# MBO.net
KiCad netlist of a schematic drawn in EAGLE
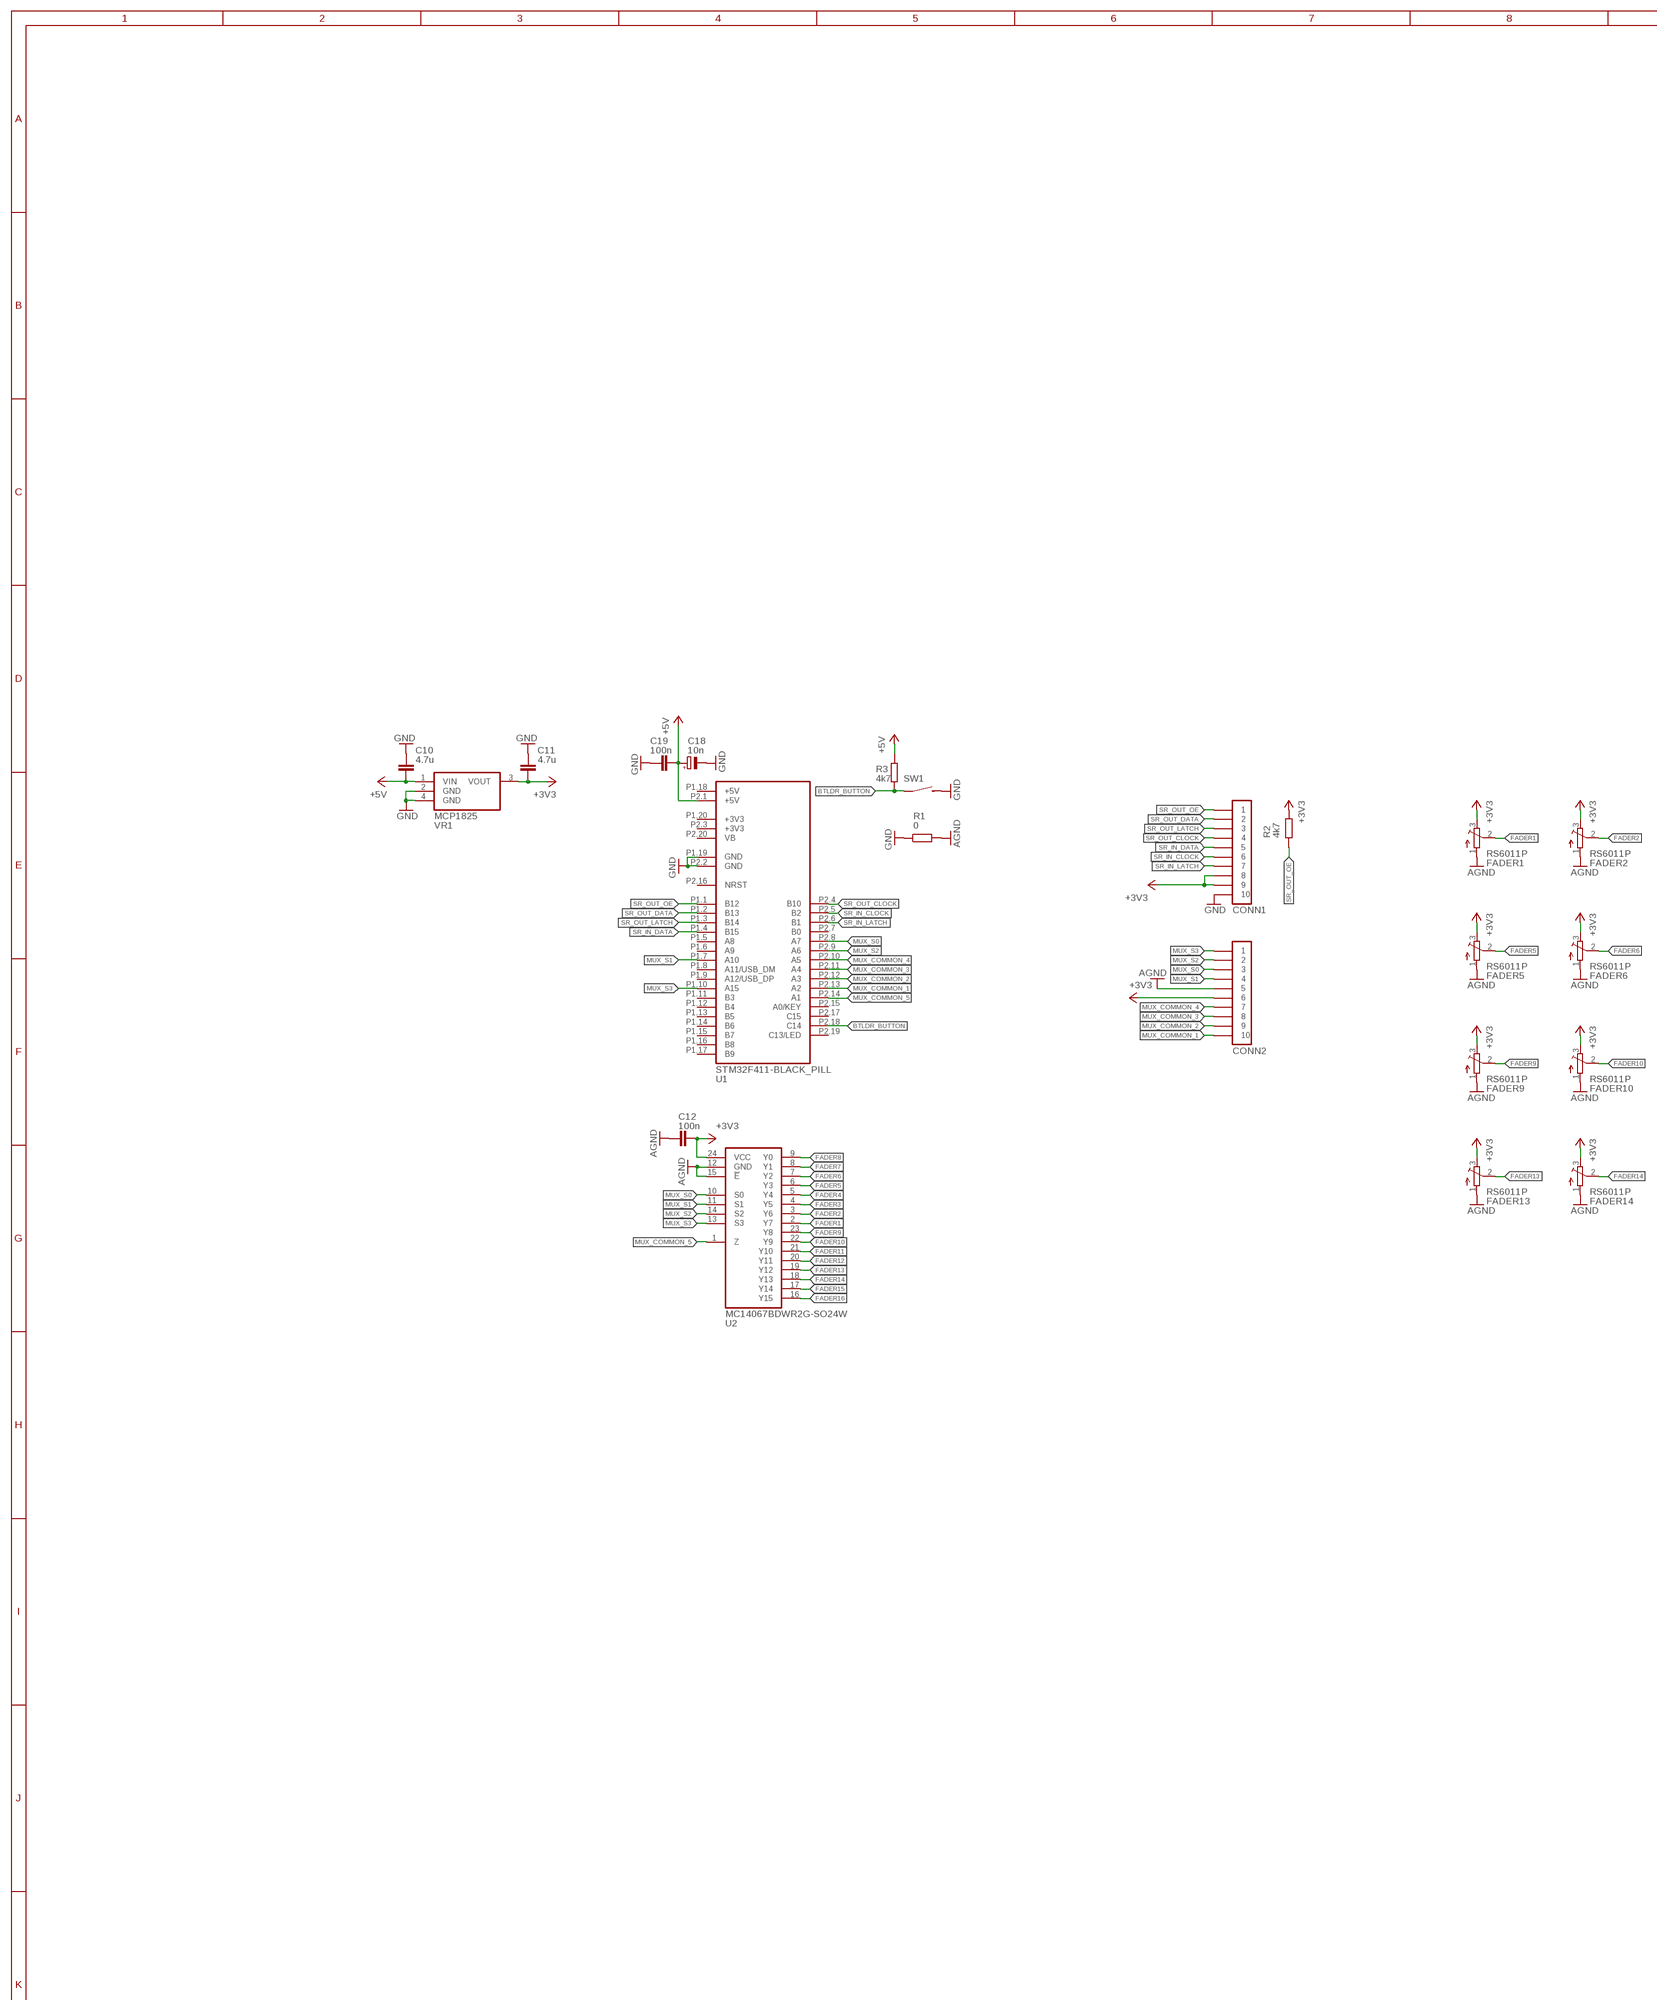
[diagram p0: schematic, sheet 1, part 1 of 3]
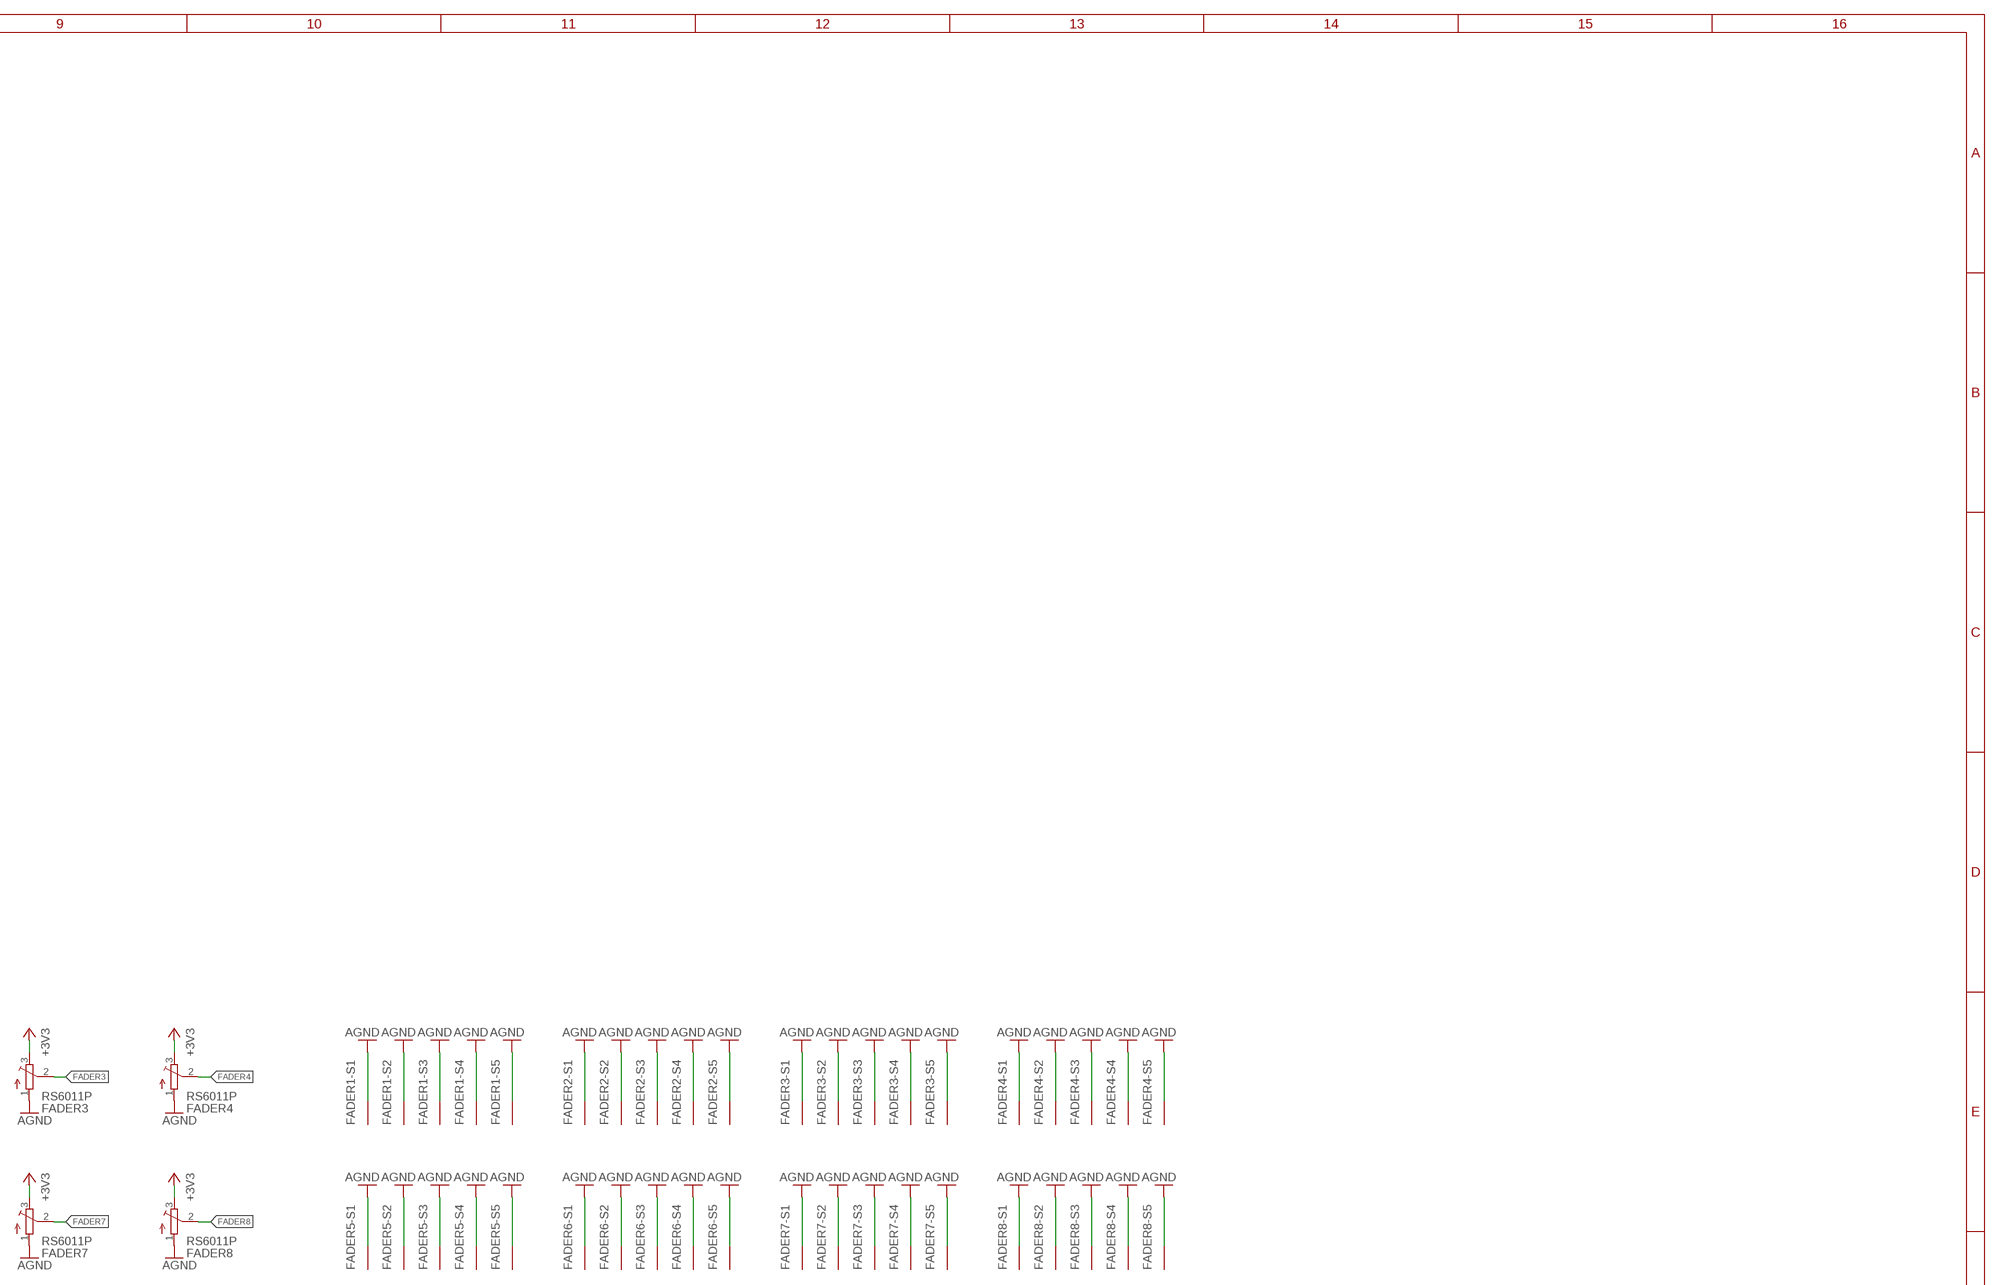
[diagram p1: schematic, sheet 1, part 2 of 3]
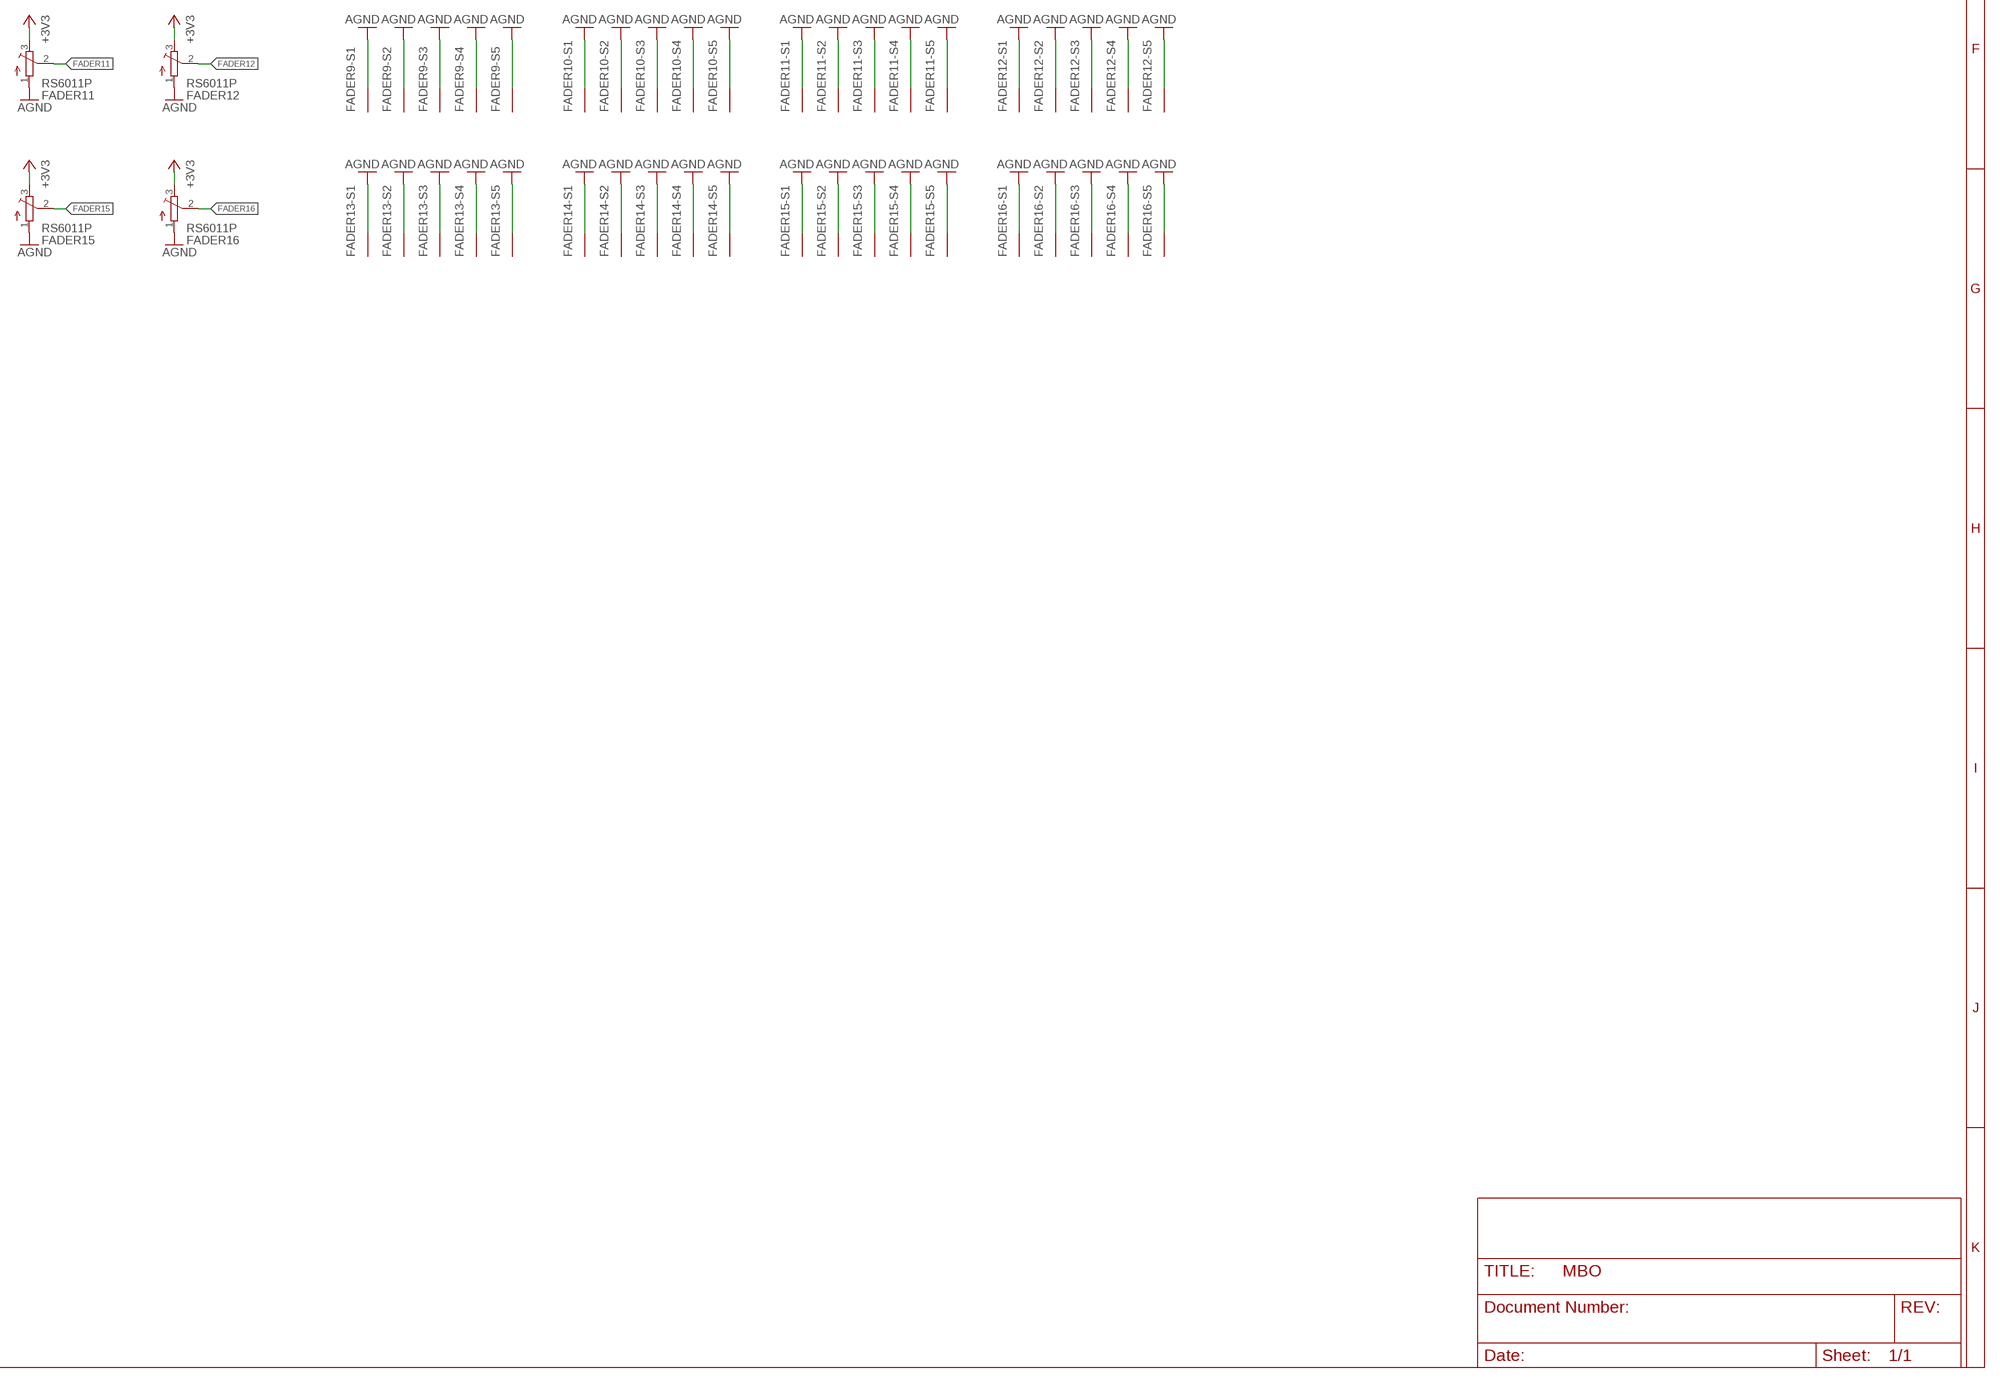
[diagram p2: schematic, sheet 1, part 3 of 3]

(export (version "E")
  (design (tool "Eeschema 10.0.6"))
  (components
    (comp (ref "C10")
      (value "4.7u")
      (footprint "eagle-import:C0805")
      (libsource (lib "eagle-import") (part "CAPACITOR-0805"))
    )
    (comp (ref "C11")
      (value "4.7u")
      (footprint "eagle-import:C0805")
      (libsource (lib "eagle-import") (part "CAPACITOR-0805"))
    )
    (comp (ref "C12")
      (value "100n")
      (footprint "eagle-import:C0805")
      (libsource (lib "eagle-import") (part "CAPACITOR-0805"))
    )
    (comp (ref "C18")
      (value "10n")
      (footprint "eagle-import:C-TH-E-0401")
      (libsource (lib "eagle-import") (part "ELECTROLYTIC_CAPACITOR-C-TH-E-0401"))
    )
    (comp (ref "C19")
      (value "100n")
      (footprint "eagle-import:C0805")
      (libsource (lib "eagle-import") (part "CAPACITOR-0805"))
    )
    (comp (ref "CONN1")
      (value "PINHD-1X10-FFC-1MM-Z")
      (footprint "eagle-import:MOLEX-52271-1079")
      (fields (field (name "MANUFACTURER") "Molex") (field (name "MPN") "52271-1079"))
      (libsource (lib "eagle-import") (part "PINHD-1X10-FFC-1MM-Z"))
    )
    (comp (ref "CONN2")
      (value "PINHD-1X10-FFC-1MM-Z")
      (footprint "eagle-import:MOLEX-52271-1079")
      (fields (field (name "MANUFACTURER") "Molex") (field (name "MPN") "52271-1079"))
      (libsource (lib "eagle-import") (part "PINHD-1X10-FFC-1MM-Z"))
    )
    (comp (ref "FADER1")
      (value "RS6011P")
      (footprint "eagle-import:RS6011_P")
      (libsource (lib "eagle-import") (part "RS6011P"))
    )
    (comp (ref "FADER2")
      (value "RS6011P")
      (footprint "eagle-import:RS6011_P")
      (libsource (lib "eagle-import") (part "RS6011P"))
    )
    (comp (ref "FADER3")
      (value "RS6011P")
      (footprint "eagle-import:RS6011_P")
      (libsource (lib "eagle-import") (part "RS6011P"))
    )
    (comp (ref "FADER4")
      (value "RS6011P")
      (footprint "eagle-import:RS6011_P")
      (libsource (lib "eagle-import") (part "RS6011P"))
    )
    (comp (ref "FADER5")
      (value "RS6011P")
      (footprint "eagle-import:RS6011_P")
      (libsource (lib "eagle-import") (part "RS6011P"))
    )
    (comp (ref "FADER6")
      (value "RS6011P")
      (footprint "eagle-import:RS6011_P")
      (libsource (lib "eagle-import") (part "RS6011P"))
    )
    (comp (ref "FADER7")
      (value "RS6011P")
      (footprint "eagle-import:RS6011_P")
      (libsource (lib "eagle-import") (part "RS6011P"))
    )
    (comp (ref "FADER8")
      (value "RS6011P")
      (footprint "eagle-import:RS6011_P")
      (libsource (lib "eagle-import") (part "RS6011P"))
    )
    (comp (ref "FADER9")
      (value "RS6011P")
      (footprint "eagle-import:RS6011_P")
      (libsource (lib "eagle-import") (part "RS6011P"))
    )
    (comp (ref "FADER10")
      (value "RS6011P")
      (footprint "eagle-import:RS6011_P")
      (libsource (lib "eagle-import") (part "RS6011P"))
    )
    (comp (ref "FADER11")
      (value "RS6011P")
      (footprint "eagle-import:RS6011_P")
      (libsource (lib "eagle-import") (part "RS6011P"))
    )
    (comp (ref "FADER12")
      (value "RS6011P")
      (footprint "eagle-import:RS6011_P")
      (libsource (lib "eagle-import") (part "RS6011P"))
    )
    (comp (ref "FADER13")
      (value "RS6011P")
      (footprint "eagle-import:RS6011_P")
      (libsource (lib "eagle-import") (part "RS6011P"))
    )
    (comp (ref "FADER14")
      (value "RS6011P")
      (footprint "eagle-import:RS6011_P")
      (libsource (lib "eagle-import") (part "RS6011P"))
    )
    (comp (ref "FADER15")
      (value "RS6011P")
      (footprint "eagle-import:RS6011_P")
      (libsource (lib "eagle-import") (part "RS6011P"))
    )
    (comp (ref "FADER16")
      (value "RS6011P")
      (footprint "eagle-import:RS6011_P")
      (libsource (lib "eagle-import") (part "RS6011P"))
    )
    (comp (ref "R1")
      (value "0")
      (footprint "eagle-import:R0805")
      (libsource (lib "eagle-import") (part "RESISTOR-0805"))
    )
    (comp (ref "R2")
      (value "4k7")
      (footprint "eagle-import:R0805")
      (libsource (lib "eagle-import") (part "RESISTOR-0805"))
    )
    (comp (ref "R3")
      (value "4k7")
      (footprint "eagle-import:R0805")
      (libsource (lib "eagle-import") (part "RESISTOR-0805"))
    )
    (comp (ref "SW1")
      (value "SWITCH-TACT-TH-6X6MM")
      (footprint "eagle-import:TACT_SW_6X6MM")
      (libsource (lib "eagle-import") (part "SWITCH-TACT-TH-6X6MM"))
    )
    (comp (ref "U1")
      (value "STM32F411-BLACK_PILL")
      (footprint "eagle-import:STM32F411-BLACK_PILL")
      (libsource (lib "eagle-import") (part "STM32F411-BLACK_PILL"))
    )
    (comp (ref "U2")
      (value "MC14067BDWR2G-SO24W")
      (footprint "eagle-import:SO24-W")
      (fields (field (name "MANUFACTURER") "ON Semiconductor") (field (name "MPN") "MC14067BDWR2G"))
      (libsource (lib "eagle-import") (part "MC14067BDWR2G-SO24W"))
    )
    (comp (ref "VR1")
      (value "MCP1825")
      (footprint "eagle-import:SOT223")
      (fields (field (name "MANUFACTURER") "Microchip") (field (name "MPN") "MCP1825S-3302E/DB"))
      (libsource (lib "eagle-import") (part "MCP1825"))
    )
  )
  (nets
    (net (code "1") (name "+3V3") (class "Default")
      (node (ref "C11") (pin "1") (pinfunction "1_1") (pintype "passive"))
      (node (ref "C12") (pin "1") (pinfunction "1_1") (pintype "passive"))
      (node (ref "CONN1") (pin "8") (pinfunction "8_8") (pintype "passive"))
      (node (ref "CONN1") (pin "9") (pinfunction "9_9") (pintype "passive"))
      (node (ref "CONN2") (pin "6") (pinfunction "6_6") (pintype "passive"))
      (node (ref "FADER1") (pin "3") (pinfunction "3_3") (pintype "passive"))
      (node (ref "FADER10") (pin "3") (pinfunction "3_3") (pintype "passive"))
      (node (ref "FADER11") (pin "3") (pinfunction "3_3") (pintype "passive"))
      (node (ref "FADER12") (pin "3") (pinfunction "3_3") (pintype "passive"))
      (node (ref "FADER13") (pin "3") (pinfunction "3_3") (pintype "passive"))
      (node (ref "FADER14") (pin "3") (pinfunction "3_3") (pintype "passive"))
      (node (ref "FADER15") (pin "3") (pinfunction "3_3") (pintype "passive"))
      (node (ref "FADER16") (pin "3") (pinfunction "3_3") (pintype "passive"))
      (node (ref "FADER2") (pin "3") (pinfunction "3_3") (pintype "passive"))
      (node (ref "FADER3") (pin "3") (pinfunction "3_3") (pintype "passive"))
      (node (ref "FADER4") (pin "3") (pinfunction "3_3") (pintype "passive"))
      (node (ref "FADER5") (pin "3") (pinfunction "3_3") (pintype "passive"))
      (node (ref "FADER6") (pin "3") (pinfunction "3_3") (pintype "passive"))
      (node (ref "FADER7") (pin "3") (pinfunction "3_3") (pintype "passive"))
      (node (ref "FADER8") (pin "3") (pinfunction "3_3") (pintype "passive"))
      (node (ref "FADER9") (pin "3") (pinfunction "3_3") (pintype "passive"))
      (node (ref "R2") (pin "2") (pinfunction "2_2") (pintype "passive"))
      (node (ref "U2") (pin "24") (pinfunction "VCC_24") (pintype "passive"))
      (node (ref "VR1") (pin "3") (pinfunction "VOUT_3") (pintype "passive"))
    )
    (net (code "2") (name "+5V") (class "Default")
      (node (ref "C10") (pin "1") (pinfunction "1_1") (pintype "passive"))
      (node (ref "C18") (pin "+") (pinfunction "+_+") (pintype "passive"))
      (node (ref "C19") (pin "1") (pinfunction "1_1") (pintype "passive"))
      (node (ref "R3") (pin "1") (pinfunction "1_1") (pintype "passive"))
      (node (ref "U1") (pin "P2.1") (pinfunction "+5V_P2.1") (pintype "bidirectional"))
      (node (ref "VR1") (pin "1") (pinfunction "VIN_1") (pintype "passive"))
    )
    (net (code "3") (name "AGND") (class "Default")
      (node (ref "C12") (pin "2") (pinfunction "2_2") (pintype "passive"))
      (node (ref "CONN2") (pin "5") (pinfunction "5_5") (pintype "passive"))
      (node (ref "FADER1") (pin "1") (pinfunction "1_1") (pintype "passive"))
      (node (ref "FADER1") (pin "S1") (pinfunction "S_S1") (pintype "passive"))
      (node (ref "FADER1") (pin "S2") (pinfunction "S_S2") (pintype "passive"))
      (node (ref "FADER1") (pin "S3") (pinfunction "S_S3") (pintype "passive"))
      (node (ref "FADER1") (pin "S4") (pinfunction "S_S4") (pintype "passive"))
      (node (ref "FADER1") (pin "S5") (pinfunction "S_S5") (pintype "passive"))
      (node (ref "FADER10") (pin "1") (pinfunction "1_1") (pintype "passive"))
      (node (ref "FADER10") (pin "S1") (pinfunction "S_S1") (pintype "passive"))
      (node (ref "FADER10") (pin "S2") (pinfunction "S_S2") (pintype "passive"))
      (node (ref "FADER10") (pin "S3") (pinfunction "S_S3") (pintype "passive"))
      (node (ref "FADER10") (pin "S4") (pinfunction "S_S4") (pintype "passive"))
      (node (ref "FADER10") (pin "S5") (pinfunction "S_S5") (pintype "passive"))
      (node (ref "FADER11") (pin "1") (pinfunction "1_1") (pintype "passive"))
      (node (ref "FADER11") (pin "S1") (pinfunction "S_S1") (pintype "passive"))
      (node (ref "FADER11") (pin "S2") (pinfunction "S_S2") (pintype "passive"))
      (node (ref "FADER11") (pin "S3") (pinfunction "S_S3") (pintype "passive"))
      (node (ref "FADER11") (pin "S4") (pinfunction "S_S4") (pintype "passive"))
      (node (ref "FADER11") (pin "S5") (pinfunction "S_S5") (pintype "passive"))
      (node (ref "FADER12") (pin "1") (pinfunction "1_1") (pintype "passive"))
      (node (ref "FADER12") (pin "S1") (pinfunction "S_S1") (pintype "passive"))
      (node (ref "FADER12") (pin "S2") (pinfunction "S_S2") (pintype "passive"))
      (node (ref "FADER12") (pin "S3") (pinfunction "S_S3") (pintype "passive"))
      (node (ref "FADER12") (pin "S4") (pinfunction "S_S4") (pintype "passive"))
      (node (ref "FADER12") (pin "S5") (pinfunction "S_S5") (pintype "passive"))
      (node (ref "FADER13") (pin "1") (pinfunction "1_1") (pintype "passive"))
      (node (ref "FADER13") (pin "S1") (pinfunction "S_S1") (pintype "passive"))
      (node (ref "FADER13") (pin "S2") (pinfunction "S_S2") (pintype "passive"))
      (node (ref "FADER13") (pin "S3") (pinfunction "S_S3") (pintype "passive"))
      (node (ref "FADER13") (pin "S4") (pinfunction "S_S4") (pintype "passive"))
      (node (ref "FADER13") (pin "S5") (pinfunction "S_S5") (pintype "passive"))
      (node (ref "FADER14") (pin "1") (pinfunction "1_1") (pintype "passive"))
      (node (ref "FADER14") (pin "S1") (pinfunction "S_S1") (pintype "passive"))
      (node (ref "FADER14") (pin "S2") (pinfunction "S_S2") (pintype "passive"))
      (node (ref "FADER14") (pin "S3") (pinfunction "S_S3") (pintype "passive"))
      (node (ref "FADER14") (pin "S4") (pinfunction "S_S4") (pintype "passive"))
      (node (ref "FADER14") (pin "S5") (pinfunction "S_S5") (pintype "passive"))
      (node (ref "FADER15") (pin "1") (pinfunction "1_1") (pintype "passive"))
      (node (ref "FADER15") (pin "S1") (pinfunction "S_S1") (pintype "passive"))
      (node (ref "FADER15") (pin "S2") (pinfunction "S_S2") (pintype "passive"))
      (node (ref "FADER15") (pin "S3") (pinfunction "S_S3") (pintype "passive"))
      (node (ref "FADER15") (pin "S4") (pinfunction "S_S4") (pintype "passive"))
      (node (ref "FADER15") (pin "S5") (pinfunction "S_S5") (pintype "passive"))
      (node (ref "FADER16") (pin "1") (pinfunction "1_1") (pintype "passive"))
      (node (ref "FADER16") (pin "S1") (pinfunction "S_S1") (pintype "passive"))
      (node (ref "FADER16") (pin "S2") (pinfunction "S_S2") (pintype "passive"))
      (node (ref "FADER16") (pin "S3") (pinfunction "S_S3") (pintype "passive"))
      (node (ref "FADER16") (pin "S4") (pinfunction "S_S4") (pintype "passive"))
      (node (ref "FADER16") (pin "S5") (pinfunction "S_S5") (pintype "passive"))
      (node (ref "FADER2") (pin "1") (pinfunction "1_1") (pintype "passive"))
      (node (ref "FADER2") (pin "S1") (pinfunction "S_S1") (pintype "passive"))
      (node (ref "FADER2") (pin "S2") (pinfunction "S_S2") (pintype "passive"))
      (node (ref "FADER2") (pin "S3") (pinfunction "S_S3") (pintype "passive"))
      (node (ref "FADER2") (pin "S4") (pinfunction "S_S4") (pintype "passive"))
      (node (ref "FADER2") (pin "S5") (pinfunction "S_S5") (pintype "passive"))
      (node (ref "FADER3") (pin "1") (pinfunction "1_1") (pintype "passive"))
      (node (ref "FADER3") (pin "S1") (pinfunction "S_S1") (pintype "passive"))
      (node (ref "FADER3") (pin "S2") (pinfunction "S_S2") (pintype "passive"))
      (node (ref "FADER3") (pin "S3") (pinfunction "S_S3") (pintype "passive"))
      (node (ref "FADER3") (pin "S4") (pinfunction "S_S4") (pintype "passive"))
      (node (ref "FADER3") (pin "S5") (pinfunction "S_S5") (pintype "passive"))
      (node (ref "FADER4") (pin "1") (pinfunction "1_1") (pintype "passive"))
      (node (ref "FADER4") (pin "S1") (pinfunction "S_S1") (pintype "passive"))
      (node (ref "FADER4") (pin "S2") (pinfunction "S_S2") (pintype "passive"))
      (node (ref "FADER4") (pin "S3") (pinfunction "S_S3") (pintype "passive"))
      (node (ref "FADER4") (pin "S4") (pinfunction "S_S4") (pintype "passive"))
      (node (ref "FADER4") (pin "S5") (pinfunction "S_S5") (pintype "passive"))
      (node (ref "FADER5") (pin "1") (pinfunction "1_1") (pintype "passive"))
      (node (ref "FADER5") (pin "S1") (pinfunction "S_S1") (pintype "passive"))
      (node (ref "FADER5") (pin "S2") (pinfunction "S_S2") (pintype "passive"))
      (node (ref "FADER5") (pin "S3") (pinfunction "S_S3") (pintype "passive"))
      (node (ref "FADER5") (pin "S4") (pinfunction "S_S4") (pintype "passive"))
      (node (ref "FADER5") (pin "S5") (pinfunction "S_S5") (pintype "passive"))
      (node (ref "FADER6") (pin "1") (pinfunction "1_1") (pintype "passive"))
      (node (ref "FADER6") (pin "S1") (pinfunction "S_S1") (pintype "passive"))
      (node (ref "FADER6") (pin "S2") (pinfunction "S_S2") (pintype "passive"))
      (node (ref "FADER6") (pin "S3") (pinfunction "S_S3") (pintype "passive"))
      (node (ref "FADER6") (pin "S4") (pinfunction "S_S4") (pintype "passive"))
      (node (ref "FADER6") (pin "S5") (pinfunction "S_S5") (pintype "passive"))
      (node (ref "FADER7") (pin "1") (pinfunction "1_1") (pintype "passive"))
      (node (ref "FADER7") (pin "S1") (pinfunction "S_S1") (pintype "passive"))
      (node (ref "FADER7") (pin "S2") (pinfunction "S_S2") (pintype "passive"))
      (node (ref "FADER7") (pin "S3") (pinfunction "S_S3") (pintype "passive"))
      (node (ref "FADER7") (pin "S4") (pinfunction "S_S4") (pintype "passive"))
      (node (ref "FADER7") (pin "S5") (pinfunction "S_S5") (pintype "passive"))
      (node (ref "FADER8") (pin "1") (pinfunction "1_1") (pintype "passive"))
      (node (ref "FADER8") (pin "S1") (pinfunction "S_S1") (pintype "passive"))
      (node (ref "FADER8") (pin "S2") (pinfunction "S_S2") (pintype "passive"))
      (node (ref "FADER8") (pin "S3") (pinfunction "S_S3") (pintype "passive"))
      (node (ref "FADER8") (pin "S4") (pinfunction "S_S4") (pintype "passive"))
      (node (ref "FADER8") (pin "S5") (pinfunction "S_S5") (pintype "passive"))
      (node (ref "FADER9") (pin "1") (pinfunction "1_1") (pintype "passive"))
      (node (ref "FADER9") (pin "S1") (pinfunction "S_S1") (pintype "passive"))
      (node (ref "FADER9") (pin "S2") (pinfunction "S_S2") (pintype "passive"))
      (node (ref "FADER9") (pin "S3") (pinfunction "S_S3") (pintype "passive"))
      (node (ref "FADER9") (pin "S4") (pinfunction "S_S4") (pintype "passive"))
      (node (ref "FADER9") (pin "S5") (pinfunction "S_S5") (pintype "passive"))
      (node (ref "R1") (pin "2") (pinfunction "2_2") (pintype "passive"))
      (node (ref "U2") (pin "12") (pinfunction "GND_12") (pintype "passive"))
      (node (ref "U2") (pin "15") (pinfunction "~{E}_15") (pintype "input"))
    )
    (net (code "4") (name "BTLDR_BUTTON") (class "Default")
      (node (ref "R3") (pin "2") (pinfunction "2_2") (pintype "passive"))
      (node (ref "SW1") (pin "A1") (pinfunction "1_A1") (pintype "passive"))
      (node (ref "U1") (pin "P2.18") (pinfunction "C14_P2.18") (pintype "bidirectional"))
    )
    (net (code "5") (name "FADER1") (class "Default")
      (node (ref "FADER1") (pin "2") (pinfunction "2_2") (pintype "passive"))
      (node (ref "U2") (pin "2") (pinfunction "Y7_2") (pintype "bidirectional"))
    )
    (net (code "6") (name "FADER2") (class "Default")
      (node (ref "FADER2") (pin "2") (pinfunction "2_2") (pintype "passive"))
      (node (ref "U2") (pin "3") (pinfunction "Y6_3") (pintype "bidirectional"))
    )
    (net (code "7") (name "FADER3") (class "Default")
      (node (ref "FADER3") (pin "2") (pinfunction "2_2") (pintype "passive"))
      (node (ref "U2") (pin "4") (pinfunction "Y5_4") (pintype "bidirectional"))
    )
    (net (code "8") (name "FADER4") (class "Default")
      (node (ref "FADER4") (pin "2") (pinfunction "2_2") (pintype "passive"))
      (node (ref "U2") (pin "5") (pinfunction "Y4_5") (pintype "bidirectional"))
    )
    (net (code "9") (name "FADER5") (class "Default")
      (node (ref "FADER5") (pin "2") (pinfunction "2_2") (pintype "passive"))
      (node (ref "U2") (pin "6") (pinfunction "Y3_6") (pintype "bidirectional"))
    )
    (net (code "10") (name "FADER6") (class "Default")
      (node (ref "FADER6") (pin "2") (pinfunction "2_2") (pintype "passive"))
      (node (ref "U2") (pin "7") (pinfunction "Y2_7") (pintype "bidirectional"))
    )
    (net (code "11") (name "FADER7") (class "Default")
      (node (ref "FADER7") (pin "2") (pinfunction "2_2") (pintype "passive"))
      (node (ref "U2") (pin "8") (pinfunction "Y1_8") (pintype "bidirectional"))
    )
    (net (code "12") (name "FADER8") (class "Default")
      (node (ref "FADER8") (pin "2") (pinfunction "2_2") (pintype "passive"))
      (node (ref "U2") (pin "9") (pinfunction "Y0_9") (pintype "bidirectional"))
    )
    (net (code "13") (name "FADER9") (class "Default")
      (node (ref "FADER9") (pin "2") (pinfunction "2_2") (pintype "passive"))
      (node (ref "U2") (pin "23") (pinfunction "Y8_23") (pintype "bidirectional"))
    )
    (net (code "14") (name "FADER10") (class "Default")
      (node (ref "FADER10") (pin "2") (pinfunction "2_2") (pintype "passive"))
      (node (ref "U2") (pin "22") (pinfunction "Y9_22") (pintype "bidirectional"))
    )
    (net (code "15") (name "FADER11") (class "Default")
      (node (ref "FADER11") (pin "2") (pinfunction "2_2") (pintype "passive"))
      (node (ref "U2") (pin "21") (pinfunction "Y10_21") (pintype "bidirectional"))
    )
    (net (code "16") (name "FADER12") (class "Default")
      (node (ref "FADER12") (pin "2") (pinfunction "2_2") (pintype "passive"))
      (node (ref "U2") (pin "20") (pinfunction "Y11_20") (pintype "bidirectional"))
    )
    (net (code "17") (name "FADER13") (class "Default")
      (node (ref "FADER13") (pin "2") (pinfunction "2_2") (pintype "passive"))
      (node (ref "U2") (pin "19") (pinfunction "Y12_19") (pintype "bidirectional"))
    )
    (net (code "18") (name "FADER14") (class "Default")
      (node (ref "FADER14") (pin "2") (pinfunction "2_2") (pintype "passive"))
      (node (ref "U2") (pin "18") (pinfunction "Y13_18") (pintype "bidirectional"))
    )
    (net (code "19") (name "FADER15") (class "Default")
      (node (ref "FADER15") (pin "2") (pinfunction "2_2") (pintype "passive"))
      (node (ref "U2") (pin "17") (pinfunction "Y14_17") (pintype "bidirectional"))
    )
    (net (code "20") (name "FADER16") (class "Default")
      (node (ref "FADER16") (pin "2") (pinfunction "2_2") (pintype "passive"))
      (node (ref "U2") (pin "16") (pinfunction "Y15_16") (pintype "bidirectional"))
    )
    (net (code "21") (name "GND") (class "Default")
      (node (ref "C10") (pin "2") (pinfunction "2_2") (pintype "passive"))
      (node (ref "C11") (pin "2") (pinfunction "2_2") (pintype "passive"))
      (node (ref "C18") (pin "-") (pinfunction "-_-") (pintype "passive"))
      (node (ref "C19") (pin "2") (pinfunction "2_2") (pintype "passive"))
      (node (ref "CONN1") (pin "10") (pinfunction "10_10") (pintype "passive"))
      (node (ref "R1") (pin "1") (pinfunction "1_1") (pintype "passive"))
      (node (ref "SW1") (pin "B1") (pinfunction "2_B1") (pintype "passive"))
      (node (ref "U1") (pin "P1.19") (pinfunction "GND_P1.19") (pintype "bidirectional"))
      (node (ref "U1") (pin "P2.2") (pinfunction "GND_P2.2") (pintype "bidirectional"))
      (node (ref "VR1") (pin "2") (pinfunction "GND_2") (pintype "passive"))
      (node (ref "VR1") (pin "4") (pinfunction "GND_4") (pintype "passive"))
    )
    (net (code "22") (name "MUX_COMMON_1") (class "Default")
      (node (ref "CONN2") (pin "10") (pinfunction "10_10") (pintype "passive"))
      (node (ref "U1") (pin "P2.13") (pinfunction "A2_P2.13") (pintype "bidirectional"))
    )
    (net (code "23") (name "MUX_COMMON_2") (class "Default")
      (node (ref "CONN2") (pin "9") (pinfunction "9_9") (pintype "passive"))
      (node (ref "U1") (pin "P2.12") (pinfunction "A3_P2.12") (pintype "bidirectional"))
    )
    (net (code "24") (name "MUX_COMMON_3") (class "Default")
      (node (ref "CONN2") (pin "8") (pinfunction "8_8") (pintype "passive"))
      (node (ref "U1") (pin "P2.11") (pinfunction "A4_P2.11") (pintype "bidirectional"))
    )
    (net (code "25") (name "MUX_COMMON_4") (class "Default")
      (node (ref "CONN2") (pin "7") (pinfunction "7_7") (pintype "passive"))
      (node (ref "U1") (pin "P2.10") (pinfunction "A5_P2.10") (pintype "bidirectional"))
    )
    (net (code "26") (name "MUX_COMMON_5") (class "Default")
      (node (ref "U1") (pin "P2.14") (pinfunction "A1_P2.14") (pintype "bidirectional"))
      (node (ref "U2") (pin "1") (pinfunction "Z_1") (pintype "bidirectional"))
    )
    (net (code "27") (name "MUX_S0") (class "Default")
      (node (ref "CONN2") (pin "3") (pinfunction "3_3") (pintype "passive"))
      (node (ref "U1") (pin "P2.8") (pinfunction "A7_P2.8") (pintype "bidirectional"))
      (node (ref "U2") (pin "10") (pinfunction "S0_10") (pintype "input"))
    )
    (net (code "28") (name "MUX_S1") (class "Default")
      (node (ref "CONN2") (pin "4") (pinfunction "4_4") (pintype "passive"))
      (node (ref "U1") (pin "P1.7") (pinfunction "A10_P1.7") (pintype "bidirectional"))
      (node (ref "U2") (pin "11") (pinfunction "S1_11") (pintype "input"))
    )
    (net (code "29") (name "MUX_S2") (class "Default")
      (node (ref "CONN2") (pin "2") (pinfunction "2_2") (pintype "passive"))
      (node (ref "U1") (pin "P2.9") (pinfunction "A6_P2.9") (pintype "bidirectional"))
      (node (ref "U2") (pin "14") (pinfunction "S2_14") (pintype "input"))
    )
    (net (code "30") (name "MUX_S3") (class "Default")
      (node (ref "CONN2") (pin "1") (pinfunction "1_1") (pintype "passive"))
      (node (ref "U1") (pin "P1.10") (pinfunction "A15_P1.10") (pintype "bidirectional"))
      (node (ref "U2") (pin "13") (pinfunction "S3_13") (pintype "input"))
    )
    (net (code "31") (name "SR_IN_CLOCK") (class "Default")
      (node (ref "CONN1") (pin "6") (pinfunction "6_6") (pintype "passive"))
      (node (ref "U1") (pin "P2.5") (pinfunction "B2_P2.5") (pintype "bidirectional"))
    )
    (net (code "32") (name "SR_IN_DATA") (class "Default")
      (node (ref "CONN1") (pin "5") (pinfunction "5_5") (pintype "passive"))
      (node (ref "U1") (pin "P1.4") (pinfunction "B15_P1.4") (pintype "bidirectional"))
    )
    (net (code "33") (name "SR_IN_LATCH") (class "Default")
      (node (ref "CONN1") (pin "7") (pinfunction "7_7") (pintype "passive"))
      (node (ref "U1") (pin "P2.6") (pinfunction "B1_P2.6") (pintype "bidirectional"))
    )
    (net (code "34") (name "SR_OUT_CLOCK") (class "Default")
      (node (ref "CONN1") (pin "4") (pinfunction "4_4") (pintype "passive"))
      (node (ref "U1") (pin "P2.4") (pinfunction "B10_P2.4") (pintype "bidirectional"))
    )
    (net (code "35") (name "SR_OUT_DATA") (class "Default")
      (node (ref "CONN1") (pin "2") (pinfunction "2_2") (pintype "passive"))
      (node (ref "U1") (pin "P1.2") (pinfunction "B13_P1.2") (pintype "bidirectional"))
    )
    (net (code "36") (name "SR_OUT_LATCH") (class "Default")
      (node (ref "CONN1") (pin "3") (pinfunction "3_3") (pintype "passive"))
      (node (ref "U1") (pin "P1.3") (pinfunction "B14_P1.3") (pintype "bidirectional"))
    )
    (net (code "37") (name "SR_OUT_OE") (class "Default")
      (node (ref "CONN1") (pin "1") (pinfunction "1_1") (pintype "passive"))
      (node (ref "R2") (pin "1") (pinfunction "1_1") (pintype "passive"))
      (node (ref "U1") (pin "P1.1") (pinfunction "B12_P1.1") (pintype "bidirectional"))
    )
    (net (code "38") (name "unconnected-(U1-+3V3-PadP1.20)") (class "Default")
      (node (ref "U1") (pin "P1.20") (pinfunction "+3V3_P1.20") (pintype "bidirectional"))
    )
    (net (code "39") (name "unconnected-(U1-+3V3-PadP2.3)") (class "Default")
      (node (ref "U1") (pin "P2.3") (pinfunction "+3V3_P2.3") (pintype "bidirectional"))
    )
    (net (code "40") (name "unconnected-(U1-+5V-PadP1.18)") (class "Default")
      (node (ref "U1") (pin "P1.18") (pinfunction "+5V_P1.18") (pintype "bidirectional"))
    )
    (net (code "41") (name "unconnected-(U1-A0{slash}KEY-PadP2.15)") (class "Default")
      (node (ref "U1") (pin "P2.15") (pinfunction "A0/KEY_P2.15") (pintype "bidirectional"))
    )
    (net (code "42") (name "unconnected-(U1-A8-PadP1.5)") (class "Default")
      (node (ref "U1") (pin "P1.5") (pinfunction "A8_P1.5") (pintype "bidirectional"))
    )
    (net (code "43") (name "unconnected-(U1-A9-PadP1.6)") (class "Default")
      (node (ref "U1") (pin "P1.6") (pinfunction "A9_P1.6") (pintype "bidirectional"))
    )
    (net (code "44") (name "unconnected-(U1-A11{slash}USB_DM-PadP1.8)") (class "Default")
      (node (ref "U1") (pin "P1.8") (pinfunction "A11/USB_DM_P1.8") (pintype "bidirectional"))
    )
    (net (code "45") (name "unconnected-(U1-A12{slash}USB_DP-PadP1.9)") (class "Default")
      (node (ref "U1") (pin "P1.9") (pinfunction "A12/USB_DP_P1.9") (pintype "bidirectional"))
    )
    (net (code "46") (name "unconnected-(U1-B0-PadP2.7)") (class "Default")
      (node (ref "U1") (pin "P2.7") (pinfunction "B0_P2.7") (pintype "bidirectional"))
    )
    (net (code "47") (name "unconnected-(U1-B3-PadP1.11)") (class "Default")
      (node (ref "U1") (pin "P1.11") (pinfunction "B3_P1.11") (pintype "bidirectional"))
    )
    (net (code "48") (name "unconnected-(U1-B4-PadP1.12)") (class "Default")
      (node (ref "U1") (pin "P1.12") (pinfunction "B4_P1.12") (pintype "bidirectional"))
    )
    (net (code "49") (name "unconnected-(U1-B5-PadP1.13)") (class "Default")
      (node (ref "U1") (pin "P1.13") (pinfunction "B5_P1.13") (pintype "bidirectional"))
    )
    (net (code "50") (name "unconnected-(U1-B6-PadP1.14)") (class "Default")
      (node (ref "U1") (pin "P1.14") (pinfunction "B6_P1.14") (pintype "bidirectional"))
    )
    (net (code "51") (name "unconnected-(U1-B7-PadP1.15)") (class "Default")
      (node (ref "U1") (pin "P1.15") (pinfunction "B7_P1.15") (pintype "bidirectional"))
    )
    (net (code "52") (name "unconnected-(U1-B8-PadP1.16)") (class "Default")
      (node (ref "U1") (pin "P1.16") (pinfunction "B8_P1.16") (pintype "bidirectional"))
    )
    (net (code "53") (name "unconnected-(U1-B9-PadP1.17)") (class "Default")
      (node (ref "U1") (pin "P1.17") (pinfunction "B9_P1.17") (pintype "bidirectional"))
    )
    (net (code "54") (name "unconnected-(U1-C13{slash}LED-PadP2.19)") (class "Default")
      (node (ref "U1") (pin "P2.19") (pinfunction "C13/LED_P2.19") (pintype "bidirectional"))
    )
    (net (code "55") (name "unconnected-(U1-C15-PadP2.17)") (class "Default")
      (node (ref "U1") (pin "P2.17") (pinfunction "C15_P2.17") (pintype "bidirectional"))
    )
    (net (code "56") (name "unconnected-(U1-NRST-PadP2.16)") (class "Default")
      (node (ref "U1") (pin "P2.16") (pinfunction "NRST_P2.16") (pintype "bidirectional"))
    )
    (net (code "57") (name "unconnected-(U1-VB-PadP2.20)") (class "Default")
      (node (ref "U1") (pin "P2.20") (pinfunction "VB_P2.20") (pintype "bidirectional"))
    )
  )
)
